# DC-DIFF-Convertor.net
KiCad netlist of a schematic drawn in Altium Designer
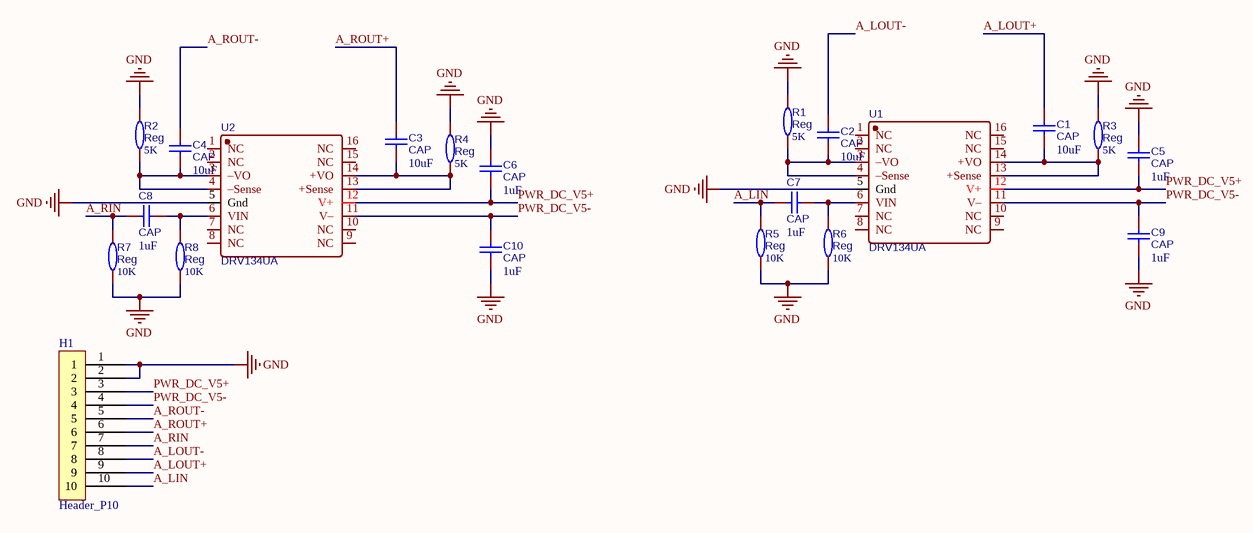
[diagram p0: DC-DIFF-Convertor.SchDoc]

(export (version "E")
  (design (tool "Eeschema 10.0.6"))
  (components
    (comp (ref "C1")
      (value "CAP")
      (footprint "C0603")
      (description "Cap")
      (fields
        (field (name "BOM_SUPPLIER PART") "C302008")
        (field (name "BOM_MANUFACTURER PART") "0603B103K101CT")
        (field (name "ALTIUM_VALUE") "10uF")
        (field (name "CONTRIBUTOR") "LCSC")
      )
      (libsource (lib "Levent_lib") (part "CAP"))
    )
    (comp (ref "C2")
      (value "CAP")
      (footprint "C0603")
      (description "Cap")
      (fields
        (field (name "BOM_SUPPLIER PART") "C302008")
        (field (name "BOM_MANUFACTURER PART") "0603B103K101CT")
        (field (name "ALTIUM_VALUE") "10uF")
        (field (name "CONTRIBUTOR") "LCSC")
      )
      (libsource (lib "Levent_lib") (part "CAP"))
    )
    (comp (ref "C3")
      (value "CAP")
      (footprint "C0603")
      (description "Cap")
      (fields
        (field (name "BOM_SUPPLIER PART") "C302008")
        (field (name "BOM_MANUFACTURER PART") "0603B103K101CT")
        (field (name "ALTIUM_VALUE") "10uF")
        (field (name "CONTRIBUTOR") "LCSC")
      )
      (libsource (lib "Levent_lib") (part "CAP"))
    )
    (comp (ref "C4")
      (value "CAP")
      (footprint "C0603")
      (description "Cap")
      (fields
        (field (name "BOM_SUPPLIER PART") "C302008")
        (field (name "BOM_MANUFACTURER PART") "0603B103K101CT")
        (field (name "ALTIUM_VALUE") "10uF")
        (field (name "CONTRIBUTOR") "LCSC")
      )
      (libsource (lib "Levent_lib") (part "CAP"))
    )
    (comp (ref "C5")
      (value "CAP")
      (footprint "C0603")
      (description "Cap")
      (fields
        (field (name "BOM_SUPPLIER PART") "C302008")
        (field (name "BOM_MANUFACTURER PART") "0603B103K101CT")
        (field (name "ALTIUM_VALUE") "1uF")
        (field (name "CONTRIBUTOR") "LCSC")
      )
      (libsource (lib "Levent_lib") (part "CAP"))
    )
    (comp (ref "C6")
      (value "CAP")
      (footprint "C0603")
      (description "Cap")
      (fields
        (field (name "BOM_SUPPLIER PART") "C302008")
        (field (name "BOM_MANUFACTURER PART") "0603B103K101CT")
        (field (name "ALTIUM_VALUE") "1uF")
        (field (name "CONTRIBUTOR") "LCSC")
      )
      (libsource (lib "Levent_lib") (part "CAP"))
    )
    (comp (ref "C7")
      (value "CAP")
      (footprint "C0603")
      (description "Cap")
      (fields
        (field (name "BOM_SUPPLIER PART") "C302008")
        (field (name "BOM_MANUFACTURER PART") "0603B103K101CT")
        (field (name "ALTIUM_VALUE") "1uF")
        (field (name "CONTRIBUTOR") "LCSC")
      )
      (libsource (lib "Levent_lib") (part "CAP"))
    )
    (comp (ref "C8")
      (value "CAP")
      (footprint "C0603")
      (description "Cap")
      (fields
        (field (name "BOM_SUPPLIER PART") "C302008")
        (field (name "BOM_MANUFACTURER PART") "0603B103K101CT")
        (field (name "ALTIUM_VALUE") "1uF")
        (field (name "CONTRIBUTOR") "LCSC")
      )
      (libsource (lib "Levent_lib") (part "CAP"))
    )
    (comp (ref "C9")
      (value "CAP")
      (footprint "C0603")
      (description "Cap")
      (fields
        (field (name "BOM_SUPPLIER PART") "C302008")
        (field (name "BOM_MANUFACTURER PART") "0603B103K101CT")
        (field (name "ALTIUM_VALUE") "1uF")
        (field (name "CONTRIBUTOR") "LCSC")
      )
      (libsource (lib "Levent_lib") (part "CAP"))
    )
    (comp (ref "C10")
      (value "CAP")
      (footprint "C0603")
      (description "Cap")
      (fields
        (field (name "BOM_SUPPLIER PART") "C302008")
        (field (name "BOM_MANUFACTURER PART") "0603B103K101CT")
        (field (name "ALTIUM_VALUE") "1uF")
        (field (name "CONTRIBUTOR") "LCSC")
      )
      (libsource (lib "Levent_lib") (part "CAP"))
    )
    (comp (ref "H1")
      (value "Header_P10")
      (footprint "H_2.54_P10")
      (description "Header 10Pin")
      (libsource (lib "Levent_lib") (part "Header_P10"))
    )
    (comp (ref "R1")
      (value "Reg")
      (footprint "R0603")
      (description "电阻")
      (fields
        (field (name "BOM_SUPPLIER PART") "C465721")
        (field (name "BOM_MANUFACTURER PART") "AR03BTCX1002A")
        (field (name "ALTIUM_VALUE") "5K")
        (field (name "CONTRIBUTOR") "LCSC")
      )
      (libsource (lib "Levent_lib") (part "Res"))
    )
    (comp (ref "R2")
      (value "Reg")
      (footprint "R0603")
      (description "电阻")
      (fields
        (field (name "BOM_SUPPLIER PART") "C465721")
        (field (name "BOM_MANUFACTURER PART") "AR03BTCX1002A")
        (field (name "ALTIUM_VALUE") "5K")
        (field (name "CONTRIBUTOR") "LCSC")
      )
      (libsource (lib "Levent_lib") (part "Res"))
    )
    (comp (ref "R3")
      (value "Reg")
      (footprint "R0603")
      (description "电阻")
      (fields
        (field (name "BOM_SUPPLIER PART") "C465721")
        (field (name "BOM_MANUFACTURER PART") "AR03BTCX1002A")
        (field (name "ALTIUM_VALUE") "5K")
        (field (name "CONTRIBUTOR") "LCSC")
      )
      (libsource (lib "Levent_lib") (part "Res"))
    )
    (comp (ref "R4")
      (value "Reg")
      (footprint "R0603")
      (description "电阻")
      (fields
        (field (name "BOM_SUPPLIER PART") "C465721")
        (field (name "BOM_MANUFACTURER PART") "AR03BTCX1002A")
        (field (name "ALTIUM_VALUE") "5K")
        (field (name "CONTRIBUTOR") "LCSC")
      )
      (libsource (lib "Levent_lib") (part "Res"))
    )
    (comp (ref "R5")
      (value "Reg")
      (footprint "R0603")
      (description "电阻")
      (fields
        (field (name "BOM_SUPPLIER PART") "C465721")
        (field (name "BOM_MANUFACTURER PART") "AR03BTCX1002A")
        (field (name "ALTIUM_VALUE") "10K")
        (field (name "CONTRIBUTOR") "LCSC")
      )
      (libsource (lib "Levent_lib") (part "Res"))
    )
    (comp (ref "R6")
      (value "Reg")
      (footprint "R0603")
      (description "电阻")
      (fields
        (field (name "BOM_SUPPLIER PART") "C465721")
        (field (name "BOM_MANUFACTURER PART") "AR03BTCX1002A")
        (field (name "ALTIUM_VALUE") "10K")
        (field (name "CONTRIBUTOR") "LCSC")
      )
      (libsource (lib "Levent_lib") (part "Res"))
    )
    (comp (ref "R7")
      (value "Reg")
      (footprint "R0603")
      (description "电阻")
      (fields
        (field (name "BOM_SUPPLIER PART") "C465721")
        (field (name "BOM_MANUFACTURER PART") "AR03BTCX1002A")
        (field (name "ALTIUM_VALUE") "10K")
        (field (name "CONTRIBUTOR") "LCSC")
      )
      (libsource (lib "Levent_lib") (part "Res"))
    )
    (comp (ref "R8")
      (value "Reg")
      (footprint "R0603")
      (description "电阻")
      (fields
        (field (name "BOM_SUPPLIER PART") "C465721")
        (field (name "BOM_MANUFACTURER PART") "AR03BTCX1002A")
        (field (name "ALTIUM_VALUE") "10K")
        (field (name "CONTRIBUTOR") "LCSC")
      )
      (libsource (lib "Levent_lib") (part "Res"))
    )
    (comp (ref "U1")
      (value "DRV134UA")
      (footprint "SOIC-16_9.5mm")
      (description "音频差分放大器")
      (fields (field (name "BOM_SUPPLIER PART") "C1519988") (field (name "CONTRIBUTOR") "LCSC"))
      (libsource (lib "Levent_lib") (part "DRV134UA"))
    )
    (comp (ref "U2")
      (value "DRV134UA")
      (footprint "SOIC-16_9.5mm")
      (description "音频差分放大器")
      (fields (field (name "BOM_SUPPLIER PART") "C1519988") (field (name "CONTRIBUTOR") "LCSC"))
      (libsource (lib "Levent_lib") (part "DRV134UA"))
    )
  )
  (nets
    (net (code "1") (name "/A_LIN") (class "Default")
      (node (ref "C7") (pin "1") (pinfunction "1_1") (pintype "passive"))
      (node (ref "H1") (pin "10") (pinfunction "10_10") (pintype "passive"))
      (node (ref "R5") (pin "2") (pinfunction "2_2") (pintype "passive"))
    )
    (net (code "2") (name "/A_LOUT+") (class "Default")
      (node (ref "C1") (pin "2") (pinfunction "2_2") (pintype "passive"))
      (node (ref "H1") (pin "9") (pinfunction "9_9") (pintype "passive"))
    )
    (net (code "3") (name "/A_LOUT-") (class "Default")
      (node (ref "C2") (pin "2") (pinfunction "2_2") (pintype "passive"))
      (node (ref "H1") (pin "8") (pinfunction "8_8") (pintype "passive"))
    )
    (net (code "4") (name "/A_RIN") (class "Default")
      (node (ref "C8") (pin "1") (pinfunction "1_1") (pintype "passive"))
      (node (ref "H1") (pin "7") (pinfunction "7_7") (pintype "passive"))
      (node (ref "R7") (pin "2") (pinfunction "2_2") (pintype "passive"))
    )
    (net (code "5") (name "/A_ROUT+") (class "Default")
      (node (ref "C3") (pin "2") (pinfunction "2_2") (pintype "passive"))
      (node (ref "H1") (pin "6") (pinfunction "6_6") (pintype "passive"))
    )
    (net (code "6") (name "/A_ROUT-") (class "Default")
      (node (ref "C4") (pin "2") (pinfunction "2_2") (pintype "passive"))
      (node (ref "H1") (pin "5") (pinfunction "5_5") (pintype "passive"))
    )
    (net (code "7") (name "/PWR_DC_V5+") (class "Default")
      (node (ref "C5") (pin "1") (pinfunction "1_1") (pintype "passive"))
      (node (ref "C6") (pin "1") (pinfunction "1_1") (pintype "passive"))
      (node (ref "H1") (pin "3") (pinfunction "3_3") (pintype "passive"))
      (node (ref "U1") (pin "12") (pinfunction "V+_12") (pintype "passive"))
      (node (ref "U2") (pin "12") (pinfunction "V+_12") (pintype "passive"))
    )
    (net (code "8") (name "/PWR_DC_V5-") (class "Default")
      (node (ref "C10") (pin "2") (pinfunction "2_2") (pintype "passive"))
      (node (ref "C9") (pin "2") (pinfunction "2_2") (pintype "passive"))
      (node (ref "H1") (pin "4") (pinfunction "4_4") (pintype "passive"))
      (node (ref "U1") (pin "11") (pinfunction "V–_11") (pintype "passive"))
      (node (ref "U2") (pin "11") (pinfunction "V–_11") (pintype "passive"))
    )
    (net (code "9") (name "GND") (class "Default")
      (node (ref "C10") (pin "1") (pinfunction "1_1") (pintype "passive"))
      (node (ref "C5") (pin "2") (pinfunction "2_2") (pintype "passive"))
      (node (ref "C6") (pin "2") (pinfunction "2_2") (pintype "passive"))
      (node (ref "C9") (pin "1") (pinfunction "1_1") (pintype "passive"))
      (node (ref "H1") (pin "1") (pinfunction "1_1") (pintype "passive"))
      (node (ref "H1") (pin "2") (pinfunction "2_2") (pintype "passive"))
      (node (ref "R1") (pin "2") (pinfunction "2_2") (pintype "passive"))
      (node (ref "R2") (pin "2") (pinfunction "2_2") (pintype "passive"))
      (node (ref "R3") (pin "1") (pinfunction "1_1") (pintype "passive"))
      (node (ref "R4") (pin "1") (pinfunction "1_1") (pintype "passive"))
      (node (ref "R5") (pin "1") (pinfunction "1_1") (pintype "passive"))
      (node (ref "R6") (pin "1") (pinfunction "1_1") (pintype "passive"))
      (node (ref "R7") (pin "1") (pinfunction "1_1") (pintype "passive"))
      (node (ref "R8") (pin "1") (pinfunction "1_1") (pintype "passive"))
      (node (ref "U1") (pin "5") (pinfunction "Gnd_5") (pintype "passive"))
      (node (ref "U2") (pin "5") (pinfunction "Gnd_5") (pintype "passive"))
    )
    (net (code "10") (name "Net-(U1-+Sense)") (class "Default")
      (node (ref "C1") (pin "1") (pinfunction "1_1") (pintype "passive"))
      (node (ref "R3") (pin "2") (pinfunction "2_2") (pintype "passive"))
      (node (ref "U1") (pin "13") (pinfunction "+Sense_13") (pintype "passive"))
      (node (ref "U1") (pin "14") (pinfunction "+VO_14") (pintype "passive"))
    )
    (net (code "11") (name "Net-(U1-VIN)") (class "Default")
      (node (ref "C7") (pin "2") (pinfunction "2_2") (pintype "passive"))
      (node (ref "R6") (pin "2") (pinfunction "2_2") (pintype "passive"))
      (node (ref "U1") (pin "6") (pinfunction "VIN_6") (pintype "passive"))
    )
    (net (code "12") (name "Net-(U1-–Sense)") (class "Default")
      (node (ref "C2") (pin "1") (pinfunction "1_1") (pintype "passive"))
      (node (ref "R1") (pin "1") (pinfunction "1_1") (pintype "passive"))
      (node (ref "U1") (pin "3") (pinfunction "–VO_3") (pintype "passive"))
      (node (ref "U1") (pin "4") (pinfunction "–Sense_4") (pintype "passive"))
    )
    (net (code "13") (name "Net-(U2-+Sense)") (class "Default")
      (node (ref "C3") (pin "1") (pinfunction "1_1") (pintype "passive"))
      (node (ref "R4") (pin "2") (pinfunction "2_2") (pintype "passive"))
      (node (ref "U2") (pin "13") (pinfunction "+Sense_13") (pintype "passive"))
      (node (ref "U2") (pin "14") (pinfunction "+VO_14") (pintype "passive"))
    )
    (net (code "14") (name "Net-(U2-VIN)") (class "Default")
      (node (ref "C8") (pin "2") (pinfunction "2_2") (pintype "passive"))
      (node (ref "R8") (pin "2") (pinfunction "2_2") (pintype "passive"))
      (node (ref "U2") (pin "6") (pinfunction "VIN_6") (pintype "passive"))
    )
    (net (code "15") (name "Net-(U2-–Sense)") (class "Default")
      (node (ref "C4") (pin "1") (pinfunction "1_1") (pintype "passive"))
      (node (ref "R2") (pin "1") (pinfunction "1_1") (pintype "passive"))
      (node (ref "U2") (pin "3") (pinfunction "–VO_3") (pintype "passive"))
      (node (ref "U2") (pin "4") (pinfunction "–Sense_4") (pintype "passive"))
    )
    (net (code "16") (name "unconnected-(U1-NC-Pad1)") (class "Default")
      (node (ref "U1") (pin "1") (pinfunction "NC_1") (pintype "passive"))
    )
    (net (code "17") (name "unconnected-(U1-NC-Pad2)") (class "Default")
      (node (ref "U1") (pin "2") (pinfunction "NC_2") (pintype "passive"))
    )
    (net (code "18") (name "unconnected-(U1-NC-Pad7)") (class "Default")
      (node (ref "U1") (pin "7") (pinfunction "NC_7") (pintype "passive"))
    )
    (net (code "19") (name "unconnected-(U1-NC-Pad8)") (class "Default")
      (node (ref "U1") (pin "8") (pinfunction "NC_8") (pintype "passive"))
    )
    (net (code "20") (name "unconnected-(U1-NC-Pad9)") (class "Default")
      (node (ref "U1") (pin "9") (pinfunction "NC_9") (pintype "passive"))
    )
    (net (code "21") (name "unconnected-(U1-NC-Pad10)") (class "Default")
      (node (ref "U1") (pin "10") (pinfunction "NC_10") (pintype "passive"))
    )
    (net (code "22") (name "unconnected-(U1-NC-Pad15)") (class "Default")
      (node (ref "U1") (pin "15") (pinfunction "NC_15") (pintype "passive"))
    )
    (net (code "23") (name "unconnected-(U1-NC-Pad16)") (class "Default")
      (node (ref "U1") (pin "16") (pinfunction "NC_16") (pintype "passive"))
    )
    (net (code "24") (name "unconnected-(U2-NC-Pad1)") (class "Default")
      (node (ref "U2") (pin "1") (pinfunction "NC_1") (pintype "passive"))
    )
    (net (code "25") (name "unconnected-(U2-NC-Pad2)") (class "Default")
      (node (ref "U2") (pin "2") (pinfunction "NC_2") (pintype "passive"))
    )
    (net (code "26") (name "unconnected-(U2-NC-Pad7)") (class "Default")
      (node (ref "U2") (pin "7") (pinfunction "NC_7") (pintype "passive"))
    )
    (net (code "27") (name "unconnected-(U2-NC-Pad8)") (class "Default")
      (node (ref "U2") (pin "8") (pinfunction "NC_8") (pintype "passive"))
    )
    (net (code "28") (name "unconnected-(U2-NC-Pad9)") (class "Default")
      (node (ref "U2") (pin "9") (pinfunction "NC_9") (pintype "passive"))
    )
    (net (code "29") (name "unconnected-(U2-NC-Pad10)") (class "Default")
      (node (ref "U2") (pin "10") (pinfunction "NC_10") (pintype "passive"))
    )
    (net (code "30") (name "unconnected-(U2-NC-Pad15)") (class "Default")
      (node (ref "U2") (pin "15") (pinfunction "NC_15") (pintype "passive"))
    )
    (net (code "31") (name "unconnected-(U2-NC-Pad16)") (class "Default")
      (node (ref "U2") (pin "16") (pinfunction "NC_16") (pintype "passive"))
    )
  )
)
